# AstroEQ_SMD_V4_7_EQ5.net
KiCad netlist of a schematic drawn in EAGLE
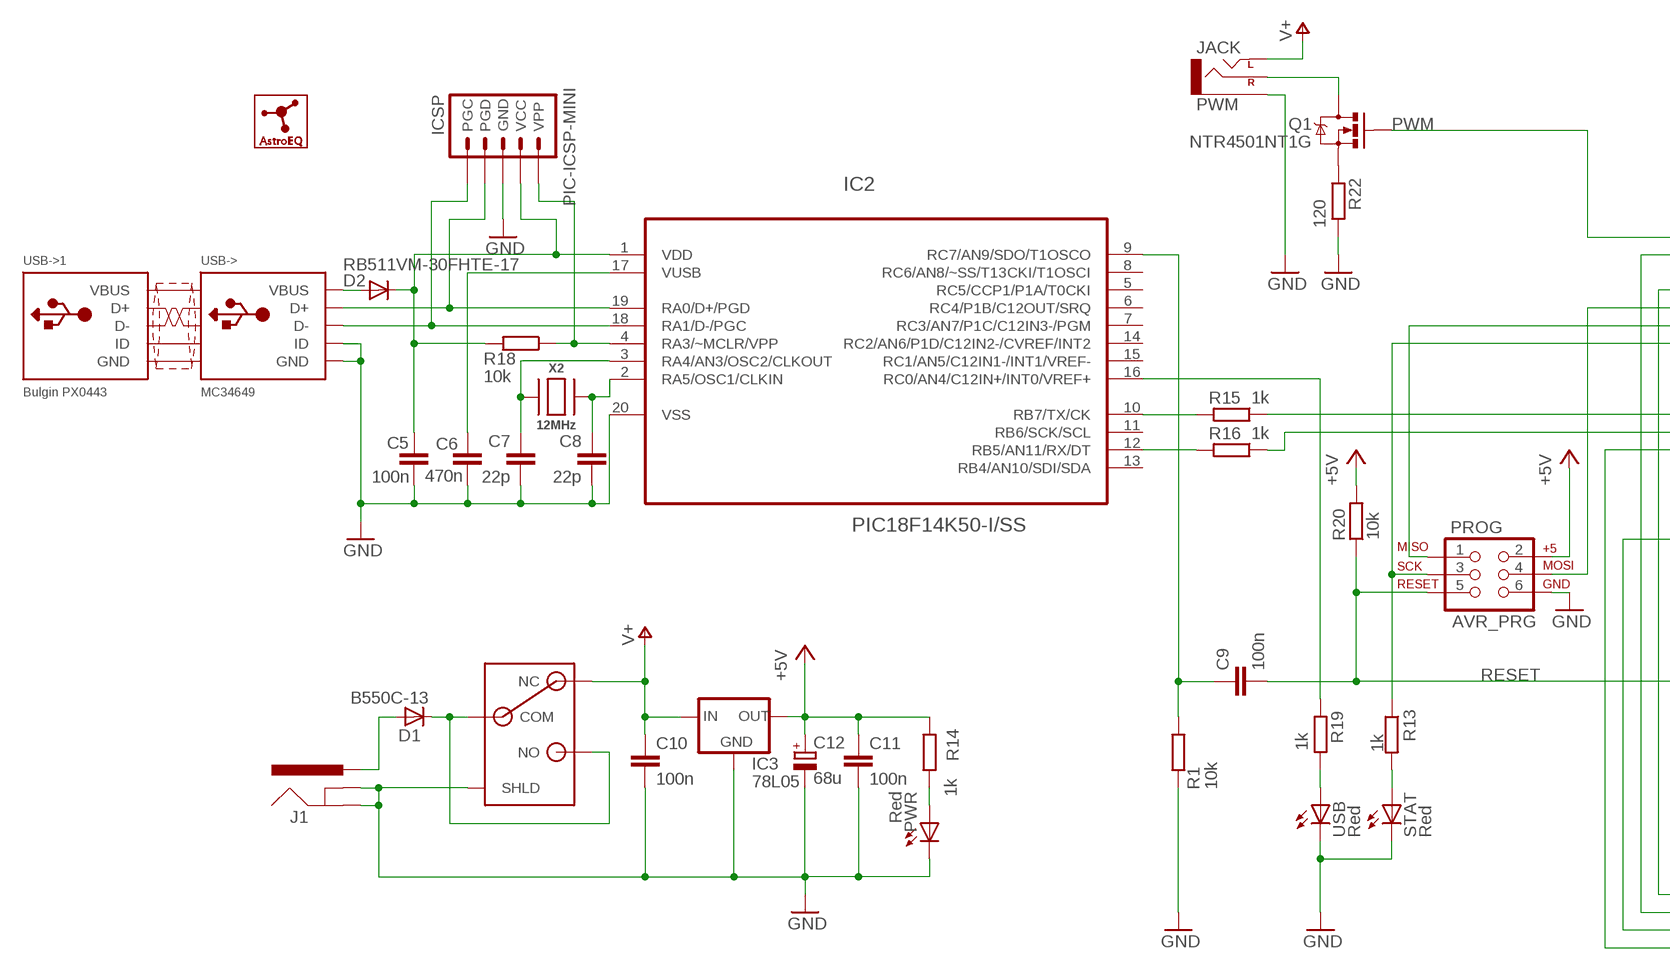
[diagram p0: schematic, sheet 1, part 1 of 2]
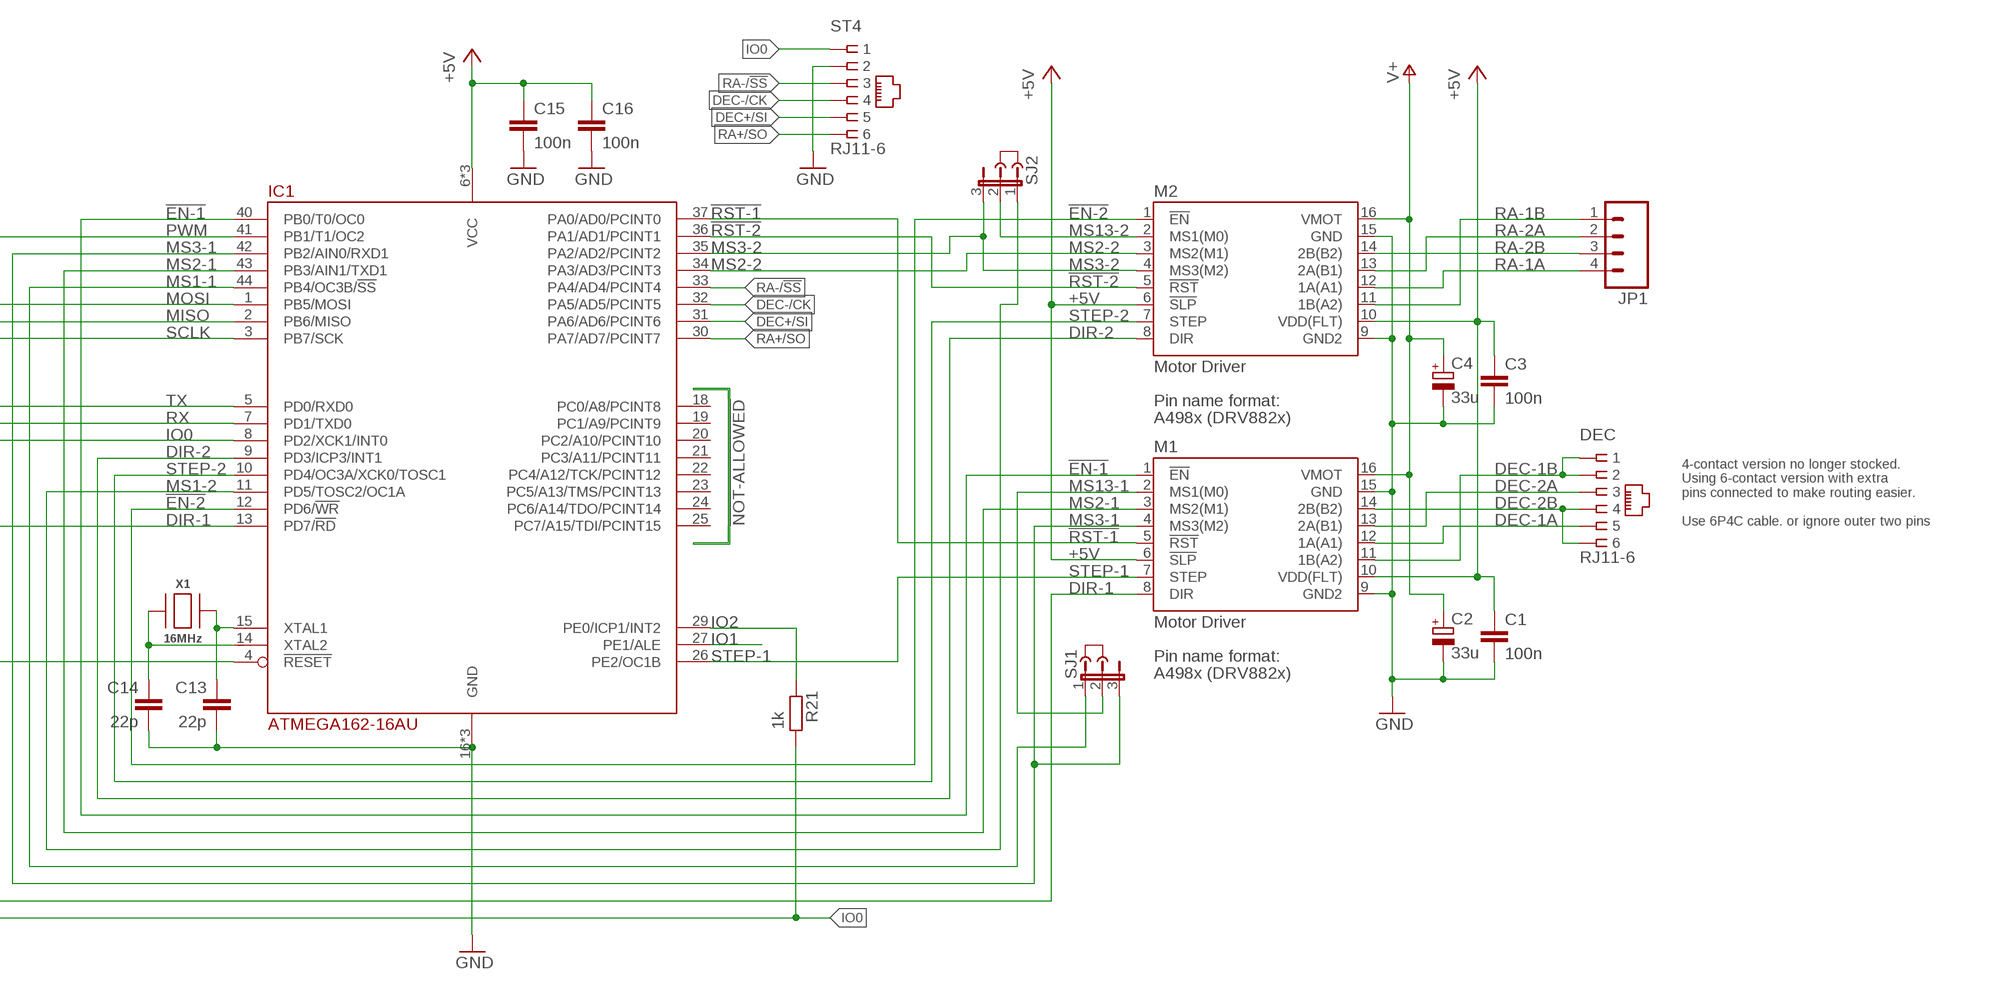
[diagram p1: schematic, sheet 1, part 2 of 2]

(export (version "E")
  (design (tool "Eeschema 10.0.6"))
  (components
    (comp (ref "C1")
      (value "100n")
      (footprint "eagle-import:C0603")
      (fields (field (name "MF") "MULTICOMP") (field (name "MPN") "MC0603F104Z250CT"))
      (libsource (lib "eagle-import") (part "C-EUC0603"))
    )
    (comp (ref "C2")
      (value "33u")
      (footprint "eagle-import:SMC_C")
      (fields (field (name "MF") "KEMET") (field (name "MPN") "T491C336K025AT"))
      (libsource (lib "eagle-import") (part "CPOL-EUSMCC"))
    )
    (comp (ref "C3")
      (value "100n")
      (footprint "eagle-import:C0603")
      (fields (field (name "MF") "MULTICOMP") (field (name "MPN") "MC0603F104Z250CT"))
      (libsource (lib "eagle-import") (part "C-EUC0603"))
    )
    (comp (ref "C4")
      (value "33u")
      (footprint "eagle-import:SMC_C")
      (fields (field (name "MF") "KEMET") (field (name "MPN") "T491C336K025AT"))
      (libsource (lib "eagle-import") (part "CPOL-EUSMCC"))
    )
    (comp (ref "C5")
      (value "100n")
      (footprint "eagle-import:C0603")
      (fields (field (name "MF") "MULTICOMP") (field (name "MPN") "MC0603F104Z250CT"))
      (libsource (lib "eagle-import") (part "C-EUC0603"))
    )
    (comp (ref "C6")
      (value "470n")
      (footprint "eagle-import:C0603")
      (fields (field (name "MF") "MULTICOMP") (field (name "MPN") "MC0603F474Z160CT"))
      (libsource (lib "eagle-import") (part "C-EUC0603"))
    )
    (comp (ref "C7")
      (value "22p")
      (footprint "eagle-import:C0603")
      (fields (field (name "MF") "MULTICOMP") (field (name "MPN") "MC0603N220J500CT"))
      (libsource (lib "eagle-import") (part "C-EUC0603"))
    )
    (comp (ref "C8")
      (value "22p")
      (footprint "eagle-import:C0603")
      (fields (field (name "MF") "MULTICOMP") (field (name "MPN") "MC0603N220J500CT"))
      (libsource (lib "eagle-import") (part "C-EUC0603"))
    )
    (comp (ref "C9")
      (value "100n")
      (footprint "eagle-import:C0603")
      (fields (field (name "MF") "MULTICOMP") (field (name "MPN") "MC0603F104Z250CT"))
      (libsource (lib "eagle-import") (part "C-EUC0603"))
    )
    (comp (ref "C10")
      (value "100n")
      (footprint "eagle-import:C0603")
      (fields (field (name "MF") "MULTICOMP") (field (name "MPN") "MC0603F104Z250CT"))
      (libsource (lib "eagle-import") (part "C-EUC0603"))
    )
    (comp (ref "C11")
      (value "100n")
      (footprint "eagle-import:C0603")
      (fields (field (name "MF") "MULTICOMP") (field (name "MPN") "MC0603F104Z250CT"))
      (libsource (lib "eagle-import") (part "C-EUC0603"))
    )
    (comp (ref "C12")
      (value "68u")
      (footprint "eagle-import:SMC_C")
      (fields (field (name "MF") "AVX") (field (name "MPN") "TPSC686K016R0125"))
      (libsource (lib "eagle-import") (part "CPOL-EUSMCC"))
    )
    (comp (ref "C13")
      (value "22p")
      (footprint "eagle-import:C0603")
      (fields (field (name "MF") "MULTICOMP") (field (name "MPN") "MC0603N220J500CT"))
      (libsource (lib "eagle-import") (part "C-EUC0603"))
    )
    (comp (ref "C14")
      (value "22p")
      (footprint "eagle-import:C0603")
      (fields (field (name "MF") "MULTICOMP") (field (name "MPN") "MC0603N220J500CT"))
      (libsource (lib "eagle-import") (part "C-EUC0603"))
    )
    (comp (ref "C15")
      (value "100n")
      (footprint "eagle-import:C0603")
      (fields (field (name "MF") "MULTICOMP") (field (name "MPN") "MC0603F104Z250CT"))
      (libsource (lib "eagle-import") (part "C-EUC0603"))
    )
    (comp (ref "C16")
      (value "100n")
      (footprint "eagle-import:C0603")
      (fields (field (name "MF") "MULTICOMP") (field (name "MPN") "MC0603F104Z250CT"))
      (libsource (lib "eagle-import") (part "C-EUC0603"))
    )
    (comp (ref "D1")
      (value "B550C-13")
      (footprint "eagle-import:SMC")
      (fields (field (name "MF") "DIODES INC.") (field (name "MPN") "B550C-13-F"))
      (libsource (lib "eagle-import") (part "DIODE-SMC"))
    )
    (comp (ref "D2")
      (value "RB511VM-30FHTE-17")
      (footprint "eagle-import:SOD-323")
      (fields (field (name "MF") "ROHM"))
      (libsource (lib "eagle-import") (part "DIODESOD"))
    )
    (comp (ref "DEC")
      (value "RJ11-6")
      (footprint "eagle-import:RJ11-NO_SHIELD")
      (fields
        (field (name "MF") "TYCO ELECTRONICS")
        (field (name "MPN") "RJ11-2L-B")
        (field (name "MF_1") "MOLEX")
        (field (name "MPN_1") "95503-2661")
        (field (name "OC_FARNELL") "1620210")
      )
      (libsource (lib "eagle-import") (part "RJ11-2L-B"))
    )
    (comp (ref "IC1")
      (value "ATMEGA162-16AU")
      (footprint "eagle-import:TQFP44")
      (fields (field (name "MF") "ATMEL"))
      (libsource (lib "eagle-import") (part "ATMEGA162-16AU"))
    )
    (comp (ref "IC2")
      (value "PIC18F14K50-I/SS")
      (footprint "eagle-import:SS20")
      (fields
        (field (name "MPN") "PIC18F14K50")
        (field (name "MF") "MICROCHIP")
        (field (name "MPN_1") "PIC18F14K50-I/SS")
        (field (name "PACKAGE") "SSOP20")
      )
      (libsource (lib "eagle-import") (part "PIC18F14K50-I/SS"))
    )
    (comp (ref "IC3")
      (value "78L05")
      (footprint "eagle-import:SOT23")
      (fields (field (name "MF") "TAIWAN SEMICONDUCTOR") (field (name "MPN") "TS78L05CX RFG"))
      (libsource (lib "eagle-import") (part "78LXXSOT-23"))
    )
    (comp (ref "ICSP")
      (value "PIC-ICSP-MINI")
      (footprint "eagle-import:PIC-ICSP-MINI")
      (libsource (lib "eagle-import") (part "PIC-ICSP-MINI"))
    )
    (comp (ref "J1")
      (value "POWER_JACKPANEL")
      (footprint "eagle-import:POWER_JACK_PANEL")
      (fields (field (name "MF") "SWITCHCRAFT") (field (name "MPN") "PCL712AS"))
      (libsource (lib "eagle-import") (part "POWER_JACKPANEL"))
    )
    (comp (ref "J2")
      (value "JUMPER")
      (footprint "eagle-import:JUMP")
      (fields (field (name "MF") "3M") (field (name "MPN") "969102-0000-DA"))
      (libsource (lib "eagle-import") (part "JUMPER"))
    )
    (comp (ref "J3")
      (value "JUMPER")
      (footprint "eagle-import:JUMP")
      (fields (field (name "MF") "3M") (field (name "MPN") "969102-0000-DA"))
      (libsource (lib "eagle-import") (part "JUMPER"))
    )
    (comp (ref "JP1")
      (value "M04POLAR")
      (footprint "eagle-import:MOLEX-1X4")
      (fields (field (name "MF") "MULTICOMP") (field (name "MPN") "MC34645"))
      (libsource (lib "eagle-import") (part "M04POLAR"))
    )
    (comp (ref "LOGO1")
      (value "ASTROEQ5MM")
      (footprint "eagle-import:ASTROEQ-SMALL")
      (libsource (lib "eagle-import") (part "ASTROEQ5MM"))
    )
    (comp (ref "M1")
      (value "Motor Driver")
      (footprint "eagle-import:DIP16-W")
      (fields (field (name "MF") "SAMTEC") (field (name "MPN") "CES-116-01-T-S"))
      (libsource (lib "eagle-import") (part "A4983CARRIER"))
    )
    (comp (ref "M2")
      (value "Motor Driver")
      (footprint "eagle-import:DIP16-W")
      (fields (field (name "MF") "SAMTEC") (field (name "MPN") "CES-116-01-T-S"))
      (libsource (lib "eagle-import") (part "A4983CARRIER"))
    )
    (comp (ref "PROG")
      (value "AVR_PRG")
      (footprint "eagle-import:2X3")
      (fields (field (name "MF") "AMP - TE CONNECTIVITY") (field (name "MPN") "826632-3"))
      (libsource (lib "eagle-import") (part "AVR_SPI_PRG_6PTH"))
    )
    (comp (ref "PWM")
      (value "JACK")
      (footprint "eagle-import:AUDIO-JACK-3.5MM-VERT")
      (fields (field (name "MANUFACTURER") "LUMBERG") (field (name "MPN") "1502 01"))
      (libsource (lib "eagle-import") (part "AUDIO-JACKVERT"))
    )
    (comp (ref "PWR")
      (value "Red")
      (footprint "eagle-import:LED3MM")
      (fields (field (name "MF") "KINGBRIGHT") (field (name "MPN") "L-424HDT"))
      (libsource (lib "eagle-import") (part "LED3MM"))
    )
    (comp (ref "PWR-SW")
      (value "SWITCH")
      (footprint "eagle-import:SPST")
      (fields (field (name "MF") "TE CONNECTIVITY") (field (name "MPN") "AE101J1V3B004"))
      (libsource (lib "eagle-import") (part "SWITCH"))
    )
    (comp (ref "Q1")
      (value "NTR4501NT1G")
      (footprint "eagle-import:SOT23-3")
      (fields (field (name "MF") "ON SEMICONDUCTOR"))
      (libsource (lib "eagle-import") (part "MOSFET-NCHANNELSMD"))
    )
    (comp (ref "R1")
      (value "10k")
      (footprint "eagle-import:R0603")
      (fields (field (name "MF") "MULTICOMP") (field (name "MPN") "MCWR06X1002FTL"))
      (libsource (lib "eagle-import") (part "rcl_R-EU_R0603"))
    )
    (comp (ref "R13")
      (value "1k")
      (footprint "eagle-import:R0603")
      (fields (field (name "MF") "MULTICOMP") (field (name "MPN") "MCWR06X1001FTL"))
      (libsource (lib "eagle-import") (part "rcl_R-EU_R0603"))
    )
    (comp (ref "R14")
      (value "1k")
      (footprint "eagle-import:R0603")
      (fields (field (name "MF") "MULTICOMP") (field (name "MPN") "MCWR06X1001FTL"))
      (libsource (lib "eagle-import") (part "rcl_R-EU_R0603"))
    )
    (comp (ref "R15")
      (value "1k")
      (footprint "eagle-import:R0603")
      (fields (field (name "MF") "MULTICOMP") (field (name "MPN") "MCWR06X1001FTL"))
      (libsource (lib "eagle-import") (part "R-EU_R0603"))
    )
    (comp (ref "R16")
      (value "1k")
      (footprint "eagle-import:R0603")
      (fields (field (name "MF") "MULTICOMP") (field (name "MPN") "MCWR06X1001FTL"))
      (libsource (lib "eagle-import") (part "R-EU_R0603"))
    )
    (comp (ref "R18")
      (value "10k")
      (footprint "eagle-import:R0603")
      (fields (field (name "MF") "MULTICOMP") (field (name "MPN") "MCWR06X1002FTL"))
      (libsource (lib "eagle-import") (part "rcl_R-EU_R0603"))
    )
    (comp (ref "R19")
      (value "1k")
      (footprint "eagle-import:R0603")
      (fields (field (name "MF") "MULTICOMP") (field (name "MPN") "MCWR06X1001FTL"))
      (libsource (lib "eagle-import") (part "rcl_R-EU_R0603"))
    )
    (comp (ref "R20")
      (value "10k")
      (footprint "eagle-import:R0603")
      (fields (field (name "MF") "MULTICOMP") (field (name "MPN") "MCWR06X1002FTL"))
      (libsource (lib "eagle-import") (part "rcl_R-EU_R0603"))
    )
    (comp (ref "R21")
      (value "1k")
      (footprint "eagle-import:R0603")
      (fields (field (name "MF") "MULTICOMP") (field (name "MPN") "MCWR06X1001FTL"))
      (libsource (lib "eagle-import") (part "rcl_R-EU_R0603"))
    )
    (comp (ref "R22")
      (value "120")
      (footprint "eagle-import:R0805")
      (fields (field (name "MF") "MULTICOMP") (field (name "MPN") "MCWR08X1200FTL"))
      (libsource (lib "eagle-import") (part "rcl_R-EU_R0805"))
    )
    (comp (ref "SJ1")
      (value "JP2E")
      (footprint "eagle-import:JP2")
      (fields (field (name "MF") "MULTICOMP") (field (name "MPN") "2211S-03G"))
      (libsource (lib "eagle-import") (part "JP2E"))
    )
    (comp (ref "SJ2")
      (value "JP2E")
      (footprint "eagle-import:JP2")
      (fields (field (name "MF") "MULTICOMP") (field (name "MPN") "2211S-03G"))
      (libsource (lib "eagle-import") (part "JP2E"))
    )
    (comp (ref "ST4")
      (value "RJ11-6")
      (footprint "eagle-import:RJ11-NO_SHIELD")
      (fields
        (field (name "MF") "TYCO ELECTRONICS")
        (field (name "MPN") "RJ11-2L-B")
        (field (name "MF_1") "MOLEX")
        (field (name "MPN_1") "95503-2661")
        (field (name "OC_FARNELL") "1620210")
      )
      (libsource (lib "eagle-import") (part "RJ11-2L-B"))
    )
    (comp (ref "STAT")
      (value "Red")
      (footprint "eagle-import:LED3MM")
      (fields (field (name "MF") "KINGBRIGHT") (field (name "MPN") "L-424HDT"))
      (libsource (lib "eagle-import") (part "LED3MM"))
    )
    (comp (ref "USB")
      (value "Red")
      (footprint "eagle-import:LED3MM")
      (fields (field (name "MF") "KINGBRIGHT") (field (name "MPN") "L-424HDT"))
      (libsource (lib "eagle-import") (part "LED3MM"))
    )
    (comp (ref "USB->")
      (value "MC34649")
      (footprint "eagle-import:22-23-2051")
      (fields (field (name "MF") "MULTICOMP"))
      (libsource (lib "eagle-import") (part "USBBULGINWIRE"))
    )
    (comp (ref "X1")
      (value "16MHz")
      (footprint "eagle-import:NX5032")
      (fields (field (name "MF") "TXC") (field (name "MPN") "7A-16.000MAAJ-T"))
      (libsource (lib "eagle-import") (part "XTALNX5032"))
    )
    (comp (ref "X2")
      (value "12MHz")
      (footprint "eagle-import:NX5032")
      (fields (field (name "MF") "TXC") (field (name "MPN") "7A-12.000MAAJ-T"))
      (libsource (lib "eagle-import") (part "XTALNX5032"))
    )
  )
  (nets
    (net (code "1") (name "+5V") (class "Default")
      (node (ref "C1") (pin "1") (pinfunction "1_1") (pintype "passive"))
      (node (ref "C11") (pin "1") (pinfunction "1_1") (pintype "passive"))
      (node (ref "C12") (pin "+") (pinfunction "+_+") (pintype "passive"))
      (node (ref "C15") (pin "1") (pinfunction "1_1") (pintype "passive"))
      (node (ref "C16") (pin "1") (pinfunction "1_1") (pintype "passive"))
      (node (ref "C3") (pin "1") (pinfunction "1_1") (pintype "passive"))
      (node (ref "IC1") (pin "17") (pinfunction "VCC_17") (pintype "power_in"))
      (node (ref "IC1") (pin "38") (pinfunction "VCC_38") (pintype "power_in"))
      (node (ref "IC1") (pin "6") (pinfunction "VCC_6") (pintype "power_in"))
      (node (ref "IC3") (pin "1") (pinfunction "OUT_1") (pintype "passive"))
      (node (ref "M1") (pin "10") (pinfunction "VDD(FLT)_10") (pintype "power_in"))
      (node (ref "M1") (pin "6") (pinfunction "~{SLP}_6") (pintype "input"))
      (node (ref "M2") (pin "10") (pinfunction "VDD(FLT)_10") (pintype "power_in"))
      (node (ref "M2") (pin "6") (pinfunction "~{SLP}_6") (pintype "input"))
      (node (ref "PROG") (pin "2") (pinfunction "2_2") (pintype "passive"))
      (node (ref "R14") (pin "1") (pinfunction "1_1") (pintype "passive"))
      (node (ref "R20") (pin "2") (pinfunction "2_2") (pintype "passive"))
    )
    (net (code "2") (name "/DEC-1A") (class "Default")
      (node (ref "DEC") (pin "5") (pinfunction "5_5") (pintype "passive"))
      (node (ref "M1") (pin "12") (pinfunction "1A(A1)_12") (pintype "output"))
    )
    (net (code "3") (name "/DEC-1B") (class "Default")
      (node (ref "DEC") (pin "1") (pinfunction "1_1") (pintype "passive"))
      (node (ref "DEC") (pin "2") (pinfunction "2_2") (pintype "passive"))
      (node (ref "M1") (pin "11") (pinfunction "1B(A2)_11") (pintype "output"))
    )
    (net (code "4") (name "/DEC-2A") (class "Default")
      (node (ref "DEC") (pin "3") (pinfunction "3_3") (pintype "passive"))
      (node (ref "M1") (pin "13") (pinfunction "2A(B1)_13") (pintype "output"))
    )
    (net (code "5") (name "/DEC-2B") (class "Default")
      (node (ref "DEC") (pin "4") (pinfunction "4_4") (pintype "passive"))
      (node (ref "DEC") (pin "6") (pinfunction "6_6") (pintype "passive"))
      (node (ref "M1") (pin "14") (pinfunction "2B(B2)_14") (pintype "output"))
    )
    (net (code "6") (name "/DIR-1") (class "Default")
      (node (ref "IC1") (pin "13") (pinfunction "PD7/~{RD}_13") (pintype "bidirectional"))
      (node (ref "M1") (pin "8") (pinfunction "DIR_8") (pintype "input"))
    )
    (net (code "7") (name "/DIR-2") (class "Default")
      (node (ref "IC1") (pin "9") (pinfunction "PD3/ICP3/INT1_9") (pintype "bidirectional"))
      (node (ref "M2") (pin "8") (pinfunction "DIR_8") (pintype "input"))
    )
    (net (code "8") (name "/IO1") (class "Default")
      (node (ref "IC1") (pin "27") (pinfunction "PE1/ALE_27") (pintype "bidirectional"))
    )
    (net (code "9") (name "/IO2") (class "Default")
      (node (ref "IC1") (pin "29") (pinfunction "PE0/ICP1/INT2_29") (pintype "bidirectional"))
      (node (ref "R21") (pin "2") (pinfunction "2_2") (pintype "passive"))
    )
    (net (code "10") (name "/MISO") (class "Default")
      (node (ref "IC1") (pin "2") (pinfunction "PB6/MISO_2") (pintype "bidirectional"))
      (node (ref "PROG") (pin "1") (pinfunction "1_1") (pintype "passive"))
    )
    (net (code "11") (name "/MOSI") (class "Default")
      (node (ref "IC1") (pin "1") (pinfunction "PB5/MOSI_1") (pintype "bidirectional"))
      (node (ref "PROG") (pin "4") (pinfunction "4_4") (pintype "passive"))
    )
    (net (code "12") (name "/MS1-1") (class "Default")
      (node (ref "IC1") (pin "44") (pinfunction "PB4/OC3B/~{SS}_44") (pintype "bidirectional"))
      (node (ref "SJ1") (pin "1") (pinfunction "1_1") (pintype "passive"))
    )
    (net (code "13") (name "/MS1-2") (class "Default")
      (node (ref "IC1") (pin "11") (pinfunction "PD5/TOSC2/OC1A_11") (pintype "bidirectional"))
      (node (ref "SJ2") (pin "1") (pinfunction "1_1") (pintype "passive"))
    )
    (net (code "14") (name "/MS2-1") (class "Default")
      (node (ref "IC1") (pin "43") (pinfunction "PB3/AIN1/TXD1_43") (pintype "bidirectional"))
      (node (ref "M1") (pin "3") (pinfunction "MS2(M1)_3") (pintype "input"))
    )
    (net (code "15") (name "/MS2-2") (class "Default")
      (node (ref "IC1") (pin "34") (pinfunction "PA3/AD3/PCINT3_34") (pintype "bidirectional"))
      (node (ref "M2") (pin "3") (pinfunction "MS2(M1)_3") (pintype "input"))
    )
    (net (code "16") (name "/MS3-1") (class "Default")
      (node (ref "IC1") (pin "42") (pinfunction "PB2/AIN0/RXD1_42") (pintype "bidirectional"))
      (node (ref "M1") (pin "4") (pinfunction "MS3(M2)_4") (pintype "input"))
      (node (ref "SJ1") (pin "3") (pinfunction "3_3") (pintype "passive"))
    )
    (net (code "17") (name "/MS3-2") (class "Default")
      (node (ref "IC1") (pin "35") (pinfunction "PA2/AD2/PCINT2_35") (pintype "bidirectional"))
      (node (ref "M2") (pin "4") (pinfunction "MS3(M2)_4") (pintype "input"))
      (node (ref "SJ2") (pin "3") (pinfunction "3_3") (pintype "passive"))
    )
    (net (code "18") (name "/MS13-1") (class "Default")
      (node (ref "M1") (pin "2") (pinfunction "MS1(M0)_2") (pintype "input"))
      (node (ref "SJ1") (pin "2") (pinfunction "2_2") (pintype "passive"))
    )
    (net (code "19") (name "/MS13-2") (class "Default")
      (node (ref "M2") (pin "2") (pinfunction "MS1(M0)_2") (pintype "input"))
      (node (ref "SJ2") (pin "2") (pinfunction "2_2") (pintype "passive"))
    )
    (net (code "20") (name "/PWM") (class "Default")
      (node (ref "IC1") (pin "41") (pinfunction "PB1/T1/OC2_41") (pintype "bidirectional"))
      (node (ref "Q1") (pin "1") (pinfunction "G_1") (pintype "passive"))
    )
    (net (code "21") (name "/RA-1A") (class "Default")
      (node (ref "JP1") (pin "4") (pinfunction "4_4") (pintype "passive"))
      (node (ref "M2") (pin "12") (pinfunction "1A(A1)_12") (pintype "output"))
    )
    (net (code "22") (name "/RA-1B") (class "Default")
      (node (ref "JP1") (pin "1") (pinfunction "1_1") (pintype "passive"))
      (node (ref "M2") (pin "11") (pinfunction "1B(A2)_11") (pintype "output"))
    )
    (net (code "23") (name "/RA-2A") (class "Default")
      (node (ref "JP1") (pin "2") (pinfunction "2_2") (pintype "passive"))
      (node (ref "M2") (pin "13") (pinfunction "2A(B1)_13") (pintype "output"))
    )
    (net (code "24") (name "/RA-2B") (class "Default")
      (node (ref "JP1") (pin "3") (pinfunction "3_3") (pintype "passive"))
      (node (ref "M2") (pin "14") (pinfunction "2B(B2)_14") (pintype "output"))
    )
    (net (code "25") (name "/RA-{slash}~{SS}") (class "Default")
      (node (ref "IC1") (pin "33") (pinfunction "PA4/AD4/PCINT4_33") (pintype "bidirectional"))
      (node (ref "ST4") (pin "3") (pinfunction "3_3") (pintype "passive"))
    )
    (net (code "26") (name "/RESET") (class "Default")
      (node (ref "C9") (pin "2") (pinfunction "2_2") (pintype "passive"))
      (node (ref "IC1") (pin "4") (pinfunction "~{RESET}_4") (pintype "input"))
      (node (ref "PROG") (pin "5") (pinfunction "5_5") (pintype "passive"))
      (node (ref "R20") (pin "1") (pinfunction "1_1") (pintype "passive"))
    )
    (net (code "27") (name "/RX") (class "Default")
      (node (ref "IC1") (pin "7") (pinfunction "PD1/TXD0_7") (pintype "bidirectional"))
      (node (ref "R16") (pin "1") (pinfunction "1_1") (pintype "passive"))
    )
    (net (code "28") (name "/SCLK") (class "Default")
      (node (ref "IC1") (pin "3") (pinfunction "PB7/SCK_3") (pintype "bidirectional"))
      (node (ref "PROG") (pin "3") (pinfunction "3_3") (pintype "passive"))
      (node (ref "R13") (pin "1") (pinfunction "1_1") (pintype "passive"))
    )
    (net (code "29") (name "/STEP-1") (class "Default")
      (node (ref "IC1") (pin "26") (pinfunction "PE2/OC1B_26") (pintype "bidirectional"))
      (node (ref "M1") (pin "7") (pinfunction "STEP_7") (pintype "input"))
    )
    (net (code "30") (name "/STEP-2") (class "Default")
      (node (ref "IC1") (pin "10") (pinfunction "PD4/OC3A/XCK0/TOSC1_10") (pintype "bidirectional"))
      (node (ref "M2") (pin "7") (pinfunction "STEP_7") (pintype "input"))
    )
    (net (code "31") (name "/TX") (class "Default")
      (node (ref "IC1") (pin "5") (pinfunction "PD0/RXD0_5") (pintype "bidirectional"))
      (node (ref "R15") (pin "1") (pinfunction "1_1") (pintype "passive"))
    )
    (net (code "32") (name "/~{EN-1}") (class "Default")
      (node (ref "IC1") (pin "40") (pinfunction "PB0/T0/OC0_40") (pintype "bidirectional"))
      (node (ref "M1") (pin "1") (pinfunction "~{EN}_1") (pintype "input"))
    )
    (net (code "33") (name "/~{EN-2}") (class "Default")
      (node (ref "IC1") (pin "12") (pinfunction "PD6/~{WR}_12") (pintype "bidirectional"))
      (node (ref "M2") (pin "1") (pinfunction "~{EN}_1") (pintype "input"))
    )
    (net (code "35") (name "/~{RST-1}") (class "Default")
      (node (ref "IC1") (pin "37") (pinfunction "PA0/AD0/PCINT0_37") (pintype "bidirectional"))
      (node (ref "M1") (pin "5") (pinfunction "~{RST}_5") (pintype "input"))
    )
    (net (code "36") (name "/~{RST-2}") (class "Default")
      (node (ref "IC1") (pin "36") (pinfunction "PA1/AD1/PCINT1_36") (pintype "bidirectional"))
      (node (ref "M2") (pin "5") (pinfunction "~{RST}_5") (pintype "input"))
    )
    (net (code "37") (name "DEC+{slash}SI") (class "Default")
      (node (ref "IC1") (pin "31") (pinfunction "PA6/AD6/PCINT6_31") (pintype "bidirectional"))
      (node (ref "ST4") (pin "5") (pinfunction "5_5") (pintype "passive"))
    )
    (net (code "38") (name "DEC-{slash}CK") (class "Default")
      (node (ref "IC1") (pin "32") (pinfunction "PA5/AD5/PCINT5_32") (pintype "bidirectional"))
      (node (ref "ST4") (pin "4") (pinfunction "4_4") (pintype "passive"))
    )
    (net (code "39") (name "GND") (class "Default")
      (node (ref "C1") (pin "2") (pinfunction "2_2") (pintype "passive"))
      (node (ref "C10") (pin "2") (pinfunction "2_2") (pintype "passive"))
      (node (ref "C11") (pin "2") (pinfunction "2_2") (pintype "passive"))
      (node (ref "C12") (pin "-") (pinfunction "-_-") (pintype "passive"))
      (node (ref "C13") (pin "2") (pinfunction "2_2") (pintype "passive"))
      (node (ref "C14") (pin "2") (pinfunction "2_2") (pintype "passive"))
      (node (ref "C15") (pin "2") (pinfunction "2_2") (pintype "passive"))
      (node (ref "C16") (pin "2") (pinfunction "2_2") (pintype "passive"))
      (node (ref "C2") (pin "-") (pinfunction "-_-") (pintype "passive"))
      (node (ref "C3") (pin "2") (pinfunction "2_2") (pintype "passive"))
      (node (ref "C4") (pin "-") (pinfunction "-_-") (pintype "passive"))
      (node (ref "C5") (pin "2") (pinfunction "2_2") (pintype "passive"))
      (node (ref "C6") (pin "1") (pinfunction "1_1") (pintype "passive"))
      (node (ref "C7") (pin "2") (pinfunction "2_2") (pintype "passive"))
      (node (ref "C8") (pin "2") (pinfunction "2_2") (pintype "passive"))
      (node (ref "IC1") (pin "16") (pinfunction "GND_16") (pintype "power_in"))
      (node (ref "IC1") (pin "28") (pinfunction "GND_28") (pintype "power_in"))
      (node (ref "IC1") (pin "39") (pinfunction "GND_39") (pintype "power_in"))
      (node (ref "IC2") (pin "20") (pinfunction "VSS_20") (pintype "power_in"))
      (node (ref "IC3") (pin "3") (pinfunction "GND_3") (pintype "input"))
      (node (ref "ICSP") (pin "3") (pinfunction "GND_3") (pintype "passive"))
      (node (ref "J1") (pin "SHUNT") (pinfunction "GNDBREAK_SHUNT") (pintype "bidirectional"))
      (node (ref "J1") (pin "SLEEVE") (pinfunction "GND_SLEEVE") (pintype "bidirectional"))
      (node (ref "M1") (pin "15") (pinfunction "GND_15") (pintype "power_in"))
      (node (ref "M1") (pin "9") (pinfunction "GND2_9") (pintype "power_in"))
      (node (ref "M2") (pin "15") (pinfunction "GND_15") (pintype "power_in"))
      (node (ref "M2") (pin "9") (pinfunction "GND2_9") (pintype "power_in"))
      (node (ref "PROG") (pin "6") (pinfunction "6_6") (pintype "passive"))
      (node (ref "PWM") (pin "1") (pinfunction "SLEEVE_1") (pintype "bidirectional"))
      (node (ref "PWR") (pin "K") (pinfunction "C_K") (pintype "passive"))
      (node (ref "PWR-SW") (pin "S1") (pinfunction "SHLD_S1") (pintype "bidirectional"))
      (node (ref "PWR-SW") (pin "S2") (pinfunction "SHLD_S2") (pintype "bidirectional"))
      (node (ref "PWR-SW") (pin "S3") (pinfunction "SHLD_S3") (pintype "bidirectional"))
      (node (ref "PWR-SW") (pin "S4") (pinfunction "SHLD_S4") (pintype "bidirectional"))
      (node (ref "R1") (pin "2") (pinfunction "2_2") (pintype "passive"))
      (node (ref "R22") (pin "1") (pinfunction "1_1") (pintype "passive"))
      (node (ref "ST4") (pin "2") (pinfunction "2_2") (pintype "passive"))
      (node (ref "STAT") (pin "K") (pinfunction "C_K") (pintype "passive"))
      (node (ref "USB") (pin "K") (pinfunction "C_K") (pintype "passive"))
      (node (ref "USB->") (pin "4") (pinfunction "GND_4") (pintype "power_in"))
      (node (ref "USB->") (pin "5") (pinfunction "ID_5") (pintype "bidirectional"))
    )
    (net (code "40") (name "IO0") (class "Default")
      (node (ref "IC1") (pin "8") (pinfunction "PD2/XCK1/INT0_8") (pintype "bidirectional"))
      (node (ref "R21") (pin "1") (pinfunction "1_1") (pintype "passive"))
      (node (ref "ST4") (pin "1") (pinfunction "1_1") (pintype "passive"))
    )
    (net (code "41") (name "Net-(D1-PadC)") (class "Default")
      (node (ref "D1") (pin "C") (pinfunction "C_C") (pintype "passive"))
      (node (ref "PWR-SW") (pin "COM") (pinfunction "COM_COM") (pintype "passive"))
      (node (ref "PWR-SW") (pin "NO") (pinfunction "NO_NO") (pintype "passive"))
    )
    (net (code "42") (name "Net-(D2-A)") (class "Default")
      (node (ref "D2") (pin "2") (pinfunction "A_2") (pintype "passive"))
      (node (ref "USB->") (pin "1") (pinfunction "VBUS_1") (pintype "power_in"))
    )
    (net (code "43") (name "Net-(D2-C)") (class "Default")
      (node (ref "C5") (pin "1") (pinfunction "1_1") (pintype "passive"))
      (node (ref "D2") (pin "1") (pinfunction "C_1") (pintype "passive"))
      (node (ref "IC2") (pin "1") (pinfunction "VDD_1") (pintype "power_in"))
      (node (ref "ICSP") (pin "2") (pinfunction "VCC_2") (pintype "passive"))
      (node (ref "R18") (pin "2") (pinfunction "2_2") (pintype "passive"))
    )
    (net (code "44") (name "Net-(IC1-XTAL1)") (class "Default")
      (node (ref "C13") (pin "1") (pinfunction "1_1") (pintype "passive"))
      (node (ref "IC1") (pin "15") (pinfunction "XTAL1_15") (pintype "input"))
      (node (ref "X1") (pin "P$1") (pinfunction "P$1_P$1") (pintype "bidirectional"))
    )
    (net (code "45") (name "Net-(IC1-XTAL2)") (class "Default")
      (node (ref "C14") (pin "1") (pinfunction "1_1") (pintype "passive"))
      (node (ref "IC1") (pin "14") (pinfunction "XTAL2_14") (pintype "input"))
      (node (ref "X1") (pin "P$2") (pinfunction "P$2_P$2") (pintype "bidirectional"))
    )
    (net (code "46") (name "Net-(IC2-RA0{slash}D+{slash}PGD)") (class "Default")
      (node (ref "IC2") (pin "19") (pinfunction "RA0/D+/PGD_19") (pintype "bidirectional"))
      (node (ref "ICSP") (pin "4") (pinfunction "PGD_4") (pintype "passive"))
      (node (ref "USB->") (pin "3") (pinfunction "D+_3") (pintype "bidirectional"))
    )
    (net (code "47") (name "Net-(IC2-RA1{slash}D-{slash}PGC)") (class "Default")
      (node (ref "IC2") (pin "18") (pinfunction "RA1/D-/PGC_18") (pintype "bidirectional"))
      (node (ref "ICSP") (pin "5") (pinfunction "PGC_5") (pintype "passive"))
      (node (ref "USB->") (pin "2") (pinfunction "D-_2") (pintype "bidirectional"))
    )
    (net (code "48") (name "Net-(IC2-RA3{slash}~{MCLR{slash}VPP})") (class "Default")
      (node (ref "IC2") (pin "4") (pinfunction "RA3/~{MCLR/VPP}_4") (pintype "input"))
      (node (ref "ICSP") (pin "1") (pinfunction "VPP_1") (pintype "passive"))
      (node (ref "R18") (pin "1") (pinfunction "1_1") (pintype "passive"))
    )
    (net (code "49") (name "Net-(IC2-RA4{slash}AN3{slash}OSC2{slash}CLKOUT)") (class "Default")
      (node (ref "C7") (pin "1") (pinfunction "1_1") (pintype "passive"))
      (node (ref "IC2") (pin "3") (pinfunction "RA4/AN3/OSC2/CLKOUT_3") (pintype "bidirectional"))
      (node (ref "X2") (pin "P$1") (pinfunction "P$1_P$1") (pintype "bidirectional"))
    )
    (net (code "50") (name "Net-(IC2-RA5{slash}OSC1{slash}CLKIN)") (class "Default")
      (node (ref "C8") (pin "1") (pinfunction "1_1") (pintype "passive"))
      (node (ref "IC2") (pin "2") (pinfunction "RA5/OSC1/CLKIN_2") (pintype "bidirectional"))
      (node (ref "X2") (pin "P$2") (pinfunction "P$2_P$2") (pintype "bidirectional"))
    )
    (net (code "51") (name "Net-(IC2-RB5{slash}AN11{slash}RX{slash}DT)") (class "Default")
      (node (ref "IC2") (pin "12") (pinfunction "RB5/AN11/RX/DT_12") (pintype "bidirectional"))
      (node (ref "R16") (pin "2") (pinfunction "2_2") (pintype "passive"))
    )
    (net (code "52") (name "Net-(IC2-RB7{slash}TX{slash}CK)") (class "Default")
      (node (ref "IC2") (pin "10") (pinfunction "RB7/TX/CK_10") (pintype "bidirectional"))
      (node (ref "R15") (pin "2") (pinfunction "2_2") (pintype "passive"))
    )
    (net (code "53") (name "Net-(IC2-RC0{slash}AN4{slash}C12IN+{slash}INT0{slash}VREF+)") (class "Default")
      (node (ref "IC2") (pin "16") (pinfunction "RC0/AN4/C12IN+/INT0/VREF+_16") (pintype "bidirectional"))
      (node (ref "R19") (pin "2") (pinfunction "2_2") (pintype "passive"))
    )
    (net (code "54") (name "Net-(IC2-RC7{slash}AN9{slash}SDO{slash}T1OSCO)") (class "Default")
      (node (ref "C9") (pin "1") (pinfunction "1_1") (pintype "passive"))
      (node (ref "IC2") (pin "9") (pinfunction "RC7/AN9/SDO/T1OSCO_9") (pintype "bidirectional"))
      (node (ref "R1") (pin "1") (pinfunction "1_1") (pintype "passive"))
    )
    (net (code "55") (name "Net-(IC2-VUSB)") (class "Default")
      (node (ref "C6") (pin "2") (pinfunction "2_2") (pintype "passive"))
      (node (ref "IC2") (pin "17") (pinfunction "VUSB_17") (pintype "power_in"))
    )
    (net (code "56") (name "Net-(J1-PWR)") (class "Default")
      (node (ref "D1") (pin "A") (pinfunction "A_A") (pintype "passive"))
      (node (ref "J1") (pin "CENTRE") (pinfunction "PWR_CENTRE") (pintype "bidirectional"))
    )
    (net (code "57") (name "Net-(PWM-RIGHT)") (class "Default")
      (node (ref "PWM") (pin "3") (pinfunction "RIGHT_3") (pintype "bidirectional"))
      (node (ref "Q1") (pin "3") (pinfunction "D_3") (pintype "passive"))
    )
    (net (code "58") (name "Net-(PWR-PadA)") (class "Default")
      (node (ref "PWR") (pin "A") (pinfunction "A_A") (pintype "passive"))
      (node (ref "R14") (pin "2") (pinfunction "2_2") (pintype "passive"))
    )
    (net (code "59") (name "Net-(Q1-S)") (class "Default")
      (node (ref "Q1") (pin "2") (pinfunction "S_2") (pintype "passive"))
      (node (ref "R22") (pin "2") (pinfunction "2_2") (pintype "passive"))
    )
    (net (code "60") (name "Net-(R13-Pad2)") (class "Default")
      (node (ref "R13") (pin "2") (pinfunction "2_2") (pintype "passive"))
      (node (ref "STAT") (pin "A") (pinfunction "A_A") (pintype "passive"))
    )
    (net (code "61") (name "Net-(R19-Pad1)") (class "Default")
      (node (ref "R19") (pin "1") (pinfunction "1_1") (pintype "passive"))
      (node (ref "USB") (pin "A") (pinfunction "A_A") (pintype "passive"))
    )
    (net (code "62") (name "RA+{slash}SO") (class "Default")
      (node (ref "IC1") (pin "30") (pinfunction "PA7/AD7/PCINT7_30") (pintype "bidirectional"))
      (node (ref "ST4") (pin "6") (pinfunction "6_6") (pintype "passive"))
    )
    (net (code "63") (name "V+") (class "Default")
      (node (ref "C10") (pin "1") (pinfunction "1_1") (pintype "passive"))
      (node (ref "C2") (pin "+") (pinfunction "+_+") (pintype "passive"))
      (node (ref "C4") (pin "+") (pinfunction "+_+") (pintype "passive"))
      (node (ref "IC3") (pin "2") (pinfunction "IN_2") (pintype "input"))
      (node (ref "M1") (pin "16") (pinfunction "VMOT_16") (pintype "power_in"))
      (node (ref "M2") (pin "16") (pinfunction "VMOT_16") (pintype "power_in"))
      (node (ref "PWM") (pin "2") (pinfunction "LEFT_2") (pintype "bidirectional"))
      (node (ref "PWR-SW") (pin "NC") (pinfunction "NC_NC") (pintype "passive"))
    )
    (net (code "64") (name "unconnected-(IC1-PC0{slash}A8{slash}PCINT8-Pad18)") (class "Default")
      (node (ref "IC1") (pin "18") (pinfunction "PC0/A8/PCINT8_18") (pintype "bidirectional"))
    )
    (net (code "65") (name "unconnected-(IC1-PC1{slash}A9{slash}PCINT9-Pad19)") (class "Default")
      (node (ref "IC1") (pin "19") (pinfunction "PC1/A9/PCINT9_19") (pintype "bidirectional"))
    )
    (net (code "66") (name "unconnected-(IC1-PC2{slash}A10{slash}PCINT10-Pad20)") (class "Default")
      (node (ref "IC1") (pin "20") (pinfunction "PC2/A10/PCINT10_20") (pintype "bidirectional"))
    )
    (net (code "67") (name "unconnected-(IC1-PC3{slash}A11{slash}PCINT11-Pad21)") (class "Default")
      (node (ref "IC1") (pin "21") (pinfunction "PC3/A11/PCINT11_21") (pintype "bidirectional"))
    )
    (net (code "68") (name "unconnected-(IC1-PC4{slash}A12{slash}TCK{slash}PCINT12-Pad22)") (class "Default")
      (node (ref "IC1") (pin "22") (pinfunction "PC4/A12/TCK/PCINT12_22") (pintype "bidirectional"))
    )
    (net (code "69") (name "unconnected-(IC1-PC5{slash}A13{slash}TMS{slash}PCINT13-Pad23)") (class "Default")
      (node (ref "IC1") (pin "23") (pinfunction "PC5/A13/TMS/PCINT13_23") (pintype "bidirectional"))
    )
    (net (code "70") (name "unconnected-(IC1-PC6{slash}A14{slash}TDO{slash}PCINT14-Pad24)") (class "Default")
      (node (ref "IC1") (pin "24") (pinfunction "PC6/A14/TDO/PCINT14_24") (pintype "bidirectional"))
    )
    (net (code "71") (name "unconnected-(IC1-PC7{slash}A15{slash}TDI{slash}PCINT15-Pad25)") (class "Default")
      (node (ref "IC1") (pin "25") (pinfunction "PC7/A15/TDI/PCINT15_25") (pintype "bidirectional"))
    )
    (net (code "72") (name "unconnected-(IC2-RB4{slash}AN10{slash}SDI{slash}SDA-Pad13)") (class "Default")
      (node (ref "IC2") (pin "13") (pinfunction "RB4/AN10/SDI/SDA_13") (pintype "bidirectional"))
    )
    (net (code "73") (name "unconnected-(IC2-RB6{slash}SCK{slash}SCL-Pad11)") (class "Default")
      (node (ref "IC2") (pin "11") (pinfunction "RB6/SCK/SCL_11") (pintype "bidirectional"))
    )
    (net (code "74") (name "unconnected-(IC2-RC1{slash}AN5{slash}C12IN1-{slash}INT1{slash}VREF--Pad15)") (class "Default")
      (node (ref "IC2") (pin "15") (pinfunction "RC1/AN5/C12IN1-/INT1/VREF-_15") (pintype "bidirectional"))
    )
    (net (code "75") (name "unconnected-(IC2-RC2{slash}AN6{slash}P1D{slash}C12IN2-{slash}CVREF{slash}INT2-Pad14)") (class "Default")
      (node (ref "IC2") (pin "14") (pinfunction "RC2/AN6/P1D/C12IN2-/CVREF/INT2_14") (pintype "bidirectional"))
    )
    (net (code "76") (name "unconnected-(IC2-RC3{slash}AN7{slash}P1C{slash}C12IN3-{slash}PGM-Pad7)") (class "Default")
      (node (ref "IC2") (pin "7") (pinfunction "RC3/AN7/P1C/C12IN3-/PGM_7") (pintype "bidirectional"))
    )
    (net (code "77") (name "unconnected-(IC2-RC4{slash}P1B{slash}C12OUT{slash}SRQ-Pad6)") (class "Default")
      (node (ref "IC2") (pin "6") (pinfunction "RC4/P1B/C12OUT/SRQ_6") (pintype "bidirectional"))
    )
    (net (code "78") (name "unconnected-(IC2-RC5{slash}CCP1{slash}P1A{slash}T0CKI-Pad5)") (class "Default")
      (node (ref "IC2") (pin "5") (pinfunction "RC5/CCP1/P1A/T0CKI_5") (pintype "bidirectional"))
    )
    (net (code "79") (name "unconnected-(IC2-RC6{slash}AN8{slash}~{SS{slash}T13CKI{slash}T1OSCI}-Pad8)") (class "Default")
      (node (ref "IC2") (pin "8") (pinfunction "RC6/AN8/~{SS/T13CKI/T1OSCI}_8") (pintype "bidirectional"))
    )
  )
)
